# 00A-002.net
KiCad netlist of a schematic drawn in EAGLE
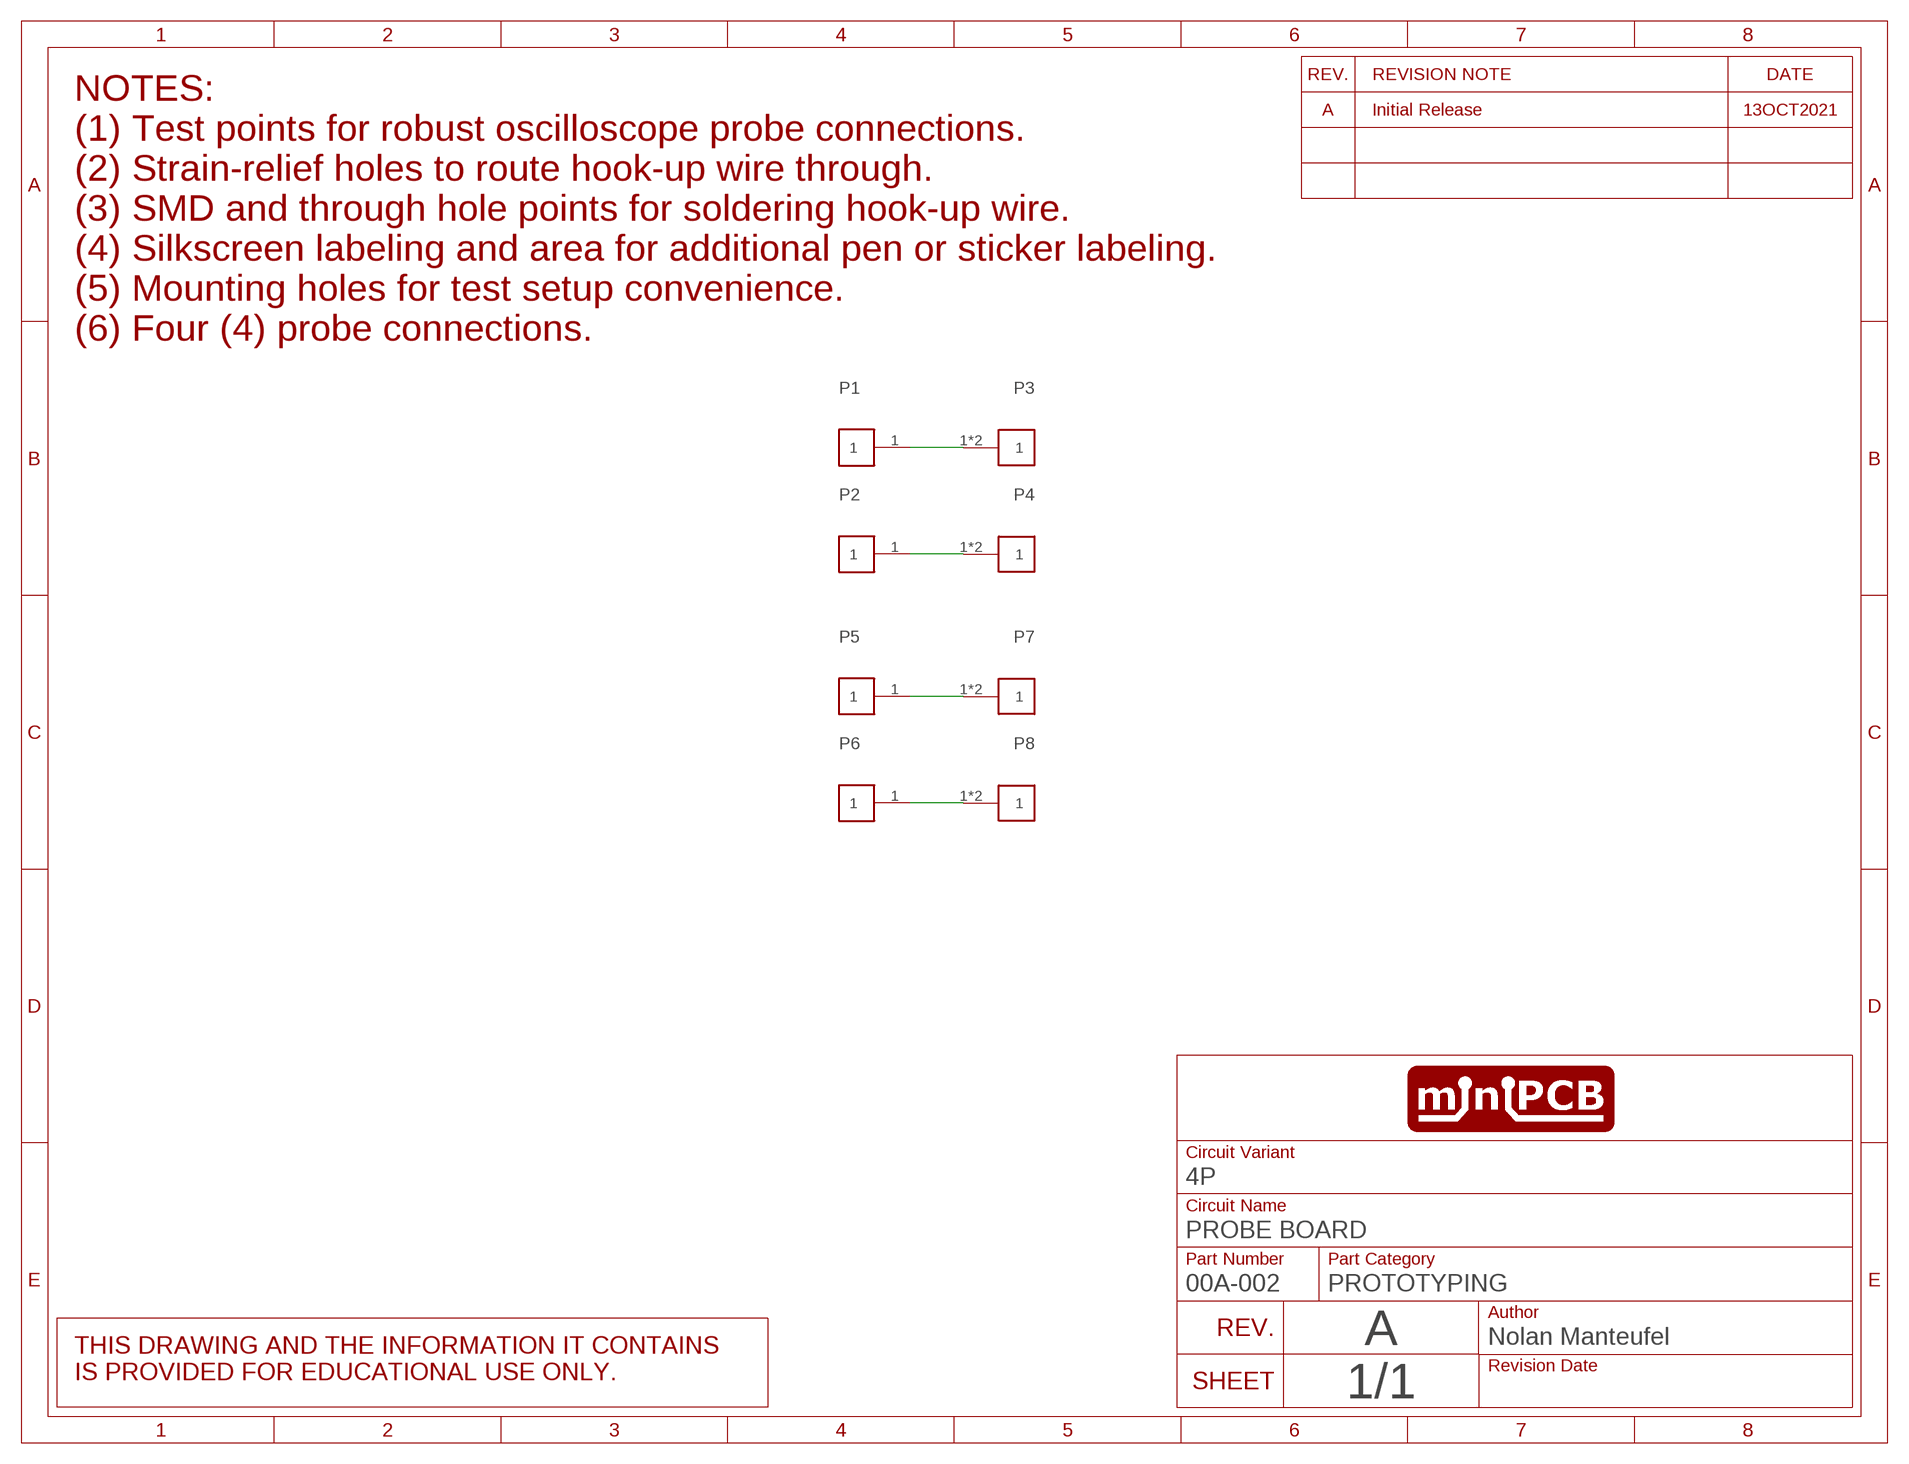
[diagram p0: schematic, sheet 1]

(export (version "E")
  (design (tool "Eeschema 10.0.6"))
  (components
    (comp (ref "P1")
      (value "PINS_1KE_5000")
      (footprint "eagle-import:PINS_1_TESTPOINT_KE5000")
      (libsource (lib "eagle-import") (part "PINS_1KE_5000"))
    )
    (comp (ref "P2")
      (value "PINS_1KE_5000")
      (footprint "eagle-import:PINS_1_TESTPOINT_KE5000")
      (libsource (lib "eagle-import") (part "PINS_1KE_5000"))
    )
    (comp (ref "P3")
      (value "PINS_124AWG")
      (footprint "eagle-import:PINS_1_1MM")
      (libsource (lib "eagle-import") (part "PINS_124AWG"))
    )
    (comp (ref "P4")
      (value "PINS_124AWG")
      (footprint "eagle-import:PINS_1_1MM")
      (libsource (lib "eagle-import") (part "PINS_124AWG"))
    )
    (comp (ref "P5")
      (value "PINS_1KE_5000")
      (footprint "eagle-import:PINS_1_TESTPOINT_KE5000")
      (libsource (lib "eagle-import") (part "PINS_1KE_5000"))
    )
    (comp (ref "P6")
      (value "PINS_1KE_5000")
      (footprint "eagle-import:PINS_1_TESTPOINT_KE5000")
      (libsource (lib "eagle-import") (part "PINS_1KE_5000"))
    )
    (comp (ref "P7")
      (value "PINS_124AWG")
      (footprint "eagle-import:PINS_1_1MM")
      (libsource (lib "eagle-import") (part "PINS_124AWG"))
    )
    (comp (ref "P8")
      (value "PINS_124AWG")
      (footprint "eagle-import:PINS_1_1MM")
      (libsource (lib "eagle-import") (part "PINS_124AWG"))
    )
  )
  (nets
    (net (code "1") (name "Net-(P1-Pad1)") (class "Default")
      (node (ref "P1") (pin "1") (pinfunction "1_1") (pintype "bidirectional"))
      (node (ref "P3") (pin "1") (pinfunction "1_1") (pintype "bidirectional"))
      (node (ref "P3") (pin "2") (pinfunction "1_2") (pintype "bidirectional"))
    )
    (net (code "2") (name "Net-(P2-Pad1)") (class "Default")
      (node (ref "P2") (pin "1") (pinfunction "1_1") (pintype "bidirectional"))
      (node (ref "P4") (pin "1") (pinfunction "1_1") (pintype "bidirectional"))
      (node (ref "P4") (pin "2") (pinfunction "1_2") (pintype "bidirectional"))
    )
    (net (code "3") (name "Net-(P5-Pad1)") (class "Default")
      (node (ref "P5") (pin "1") (pinfunction "1_1") (pintype "bidirectional"))
      (node (ref "P7") (pin "1") (pinfunction "1_1") (pintype "bidirectional"))
      (node (ref "P7") (pin "2") (pinfunction "1_2") (pintype "bidirectional"))
    )
    (net (code "4") (name "Net-(P6-Pad1)") (class "Default")
      (node (ref "P6") (pin "1") (pinfunction "1_1") (pintype "bidirectional"))
      (node (ref "P8") (pin "1") (pinfunction "1_1") (pintype "bidirectional"))
      (node (ref "P8") (pin "2") (pinfunction "1_2") (pintype "bidirectional"))
    )
  )
)
